# js220_fp_banana.net
KiCad netlist of a schematic drawn in EAGLE
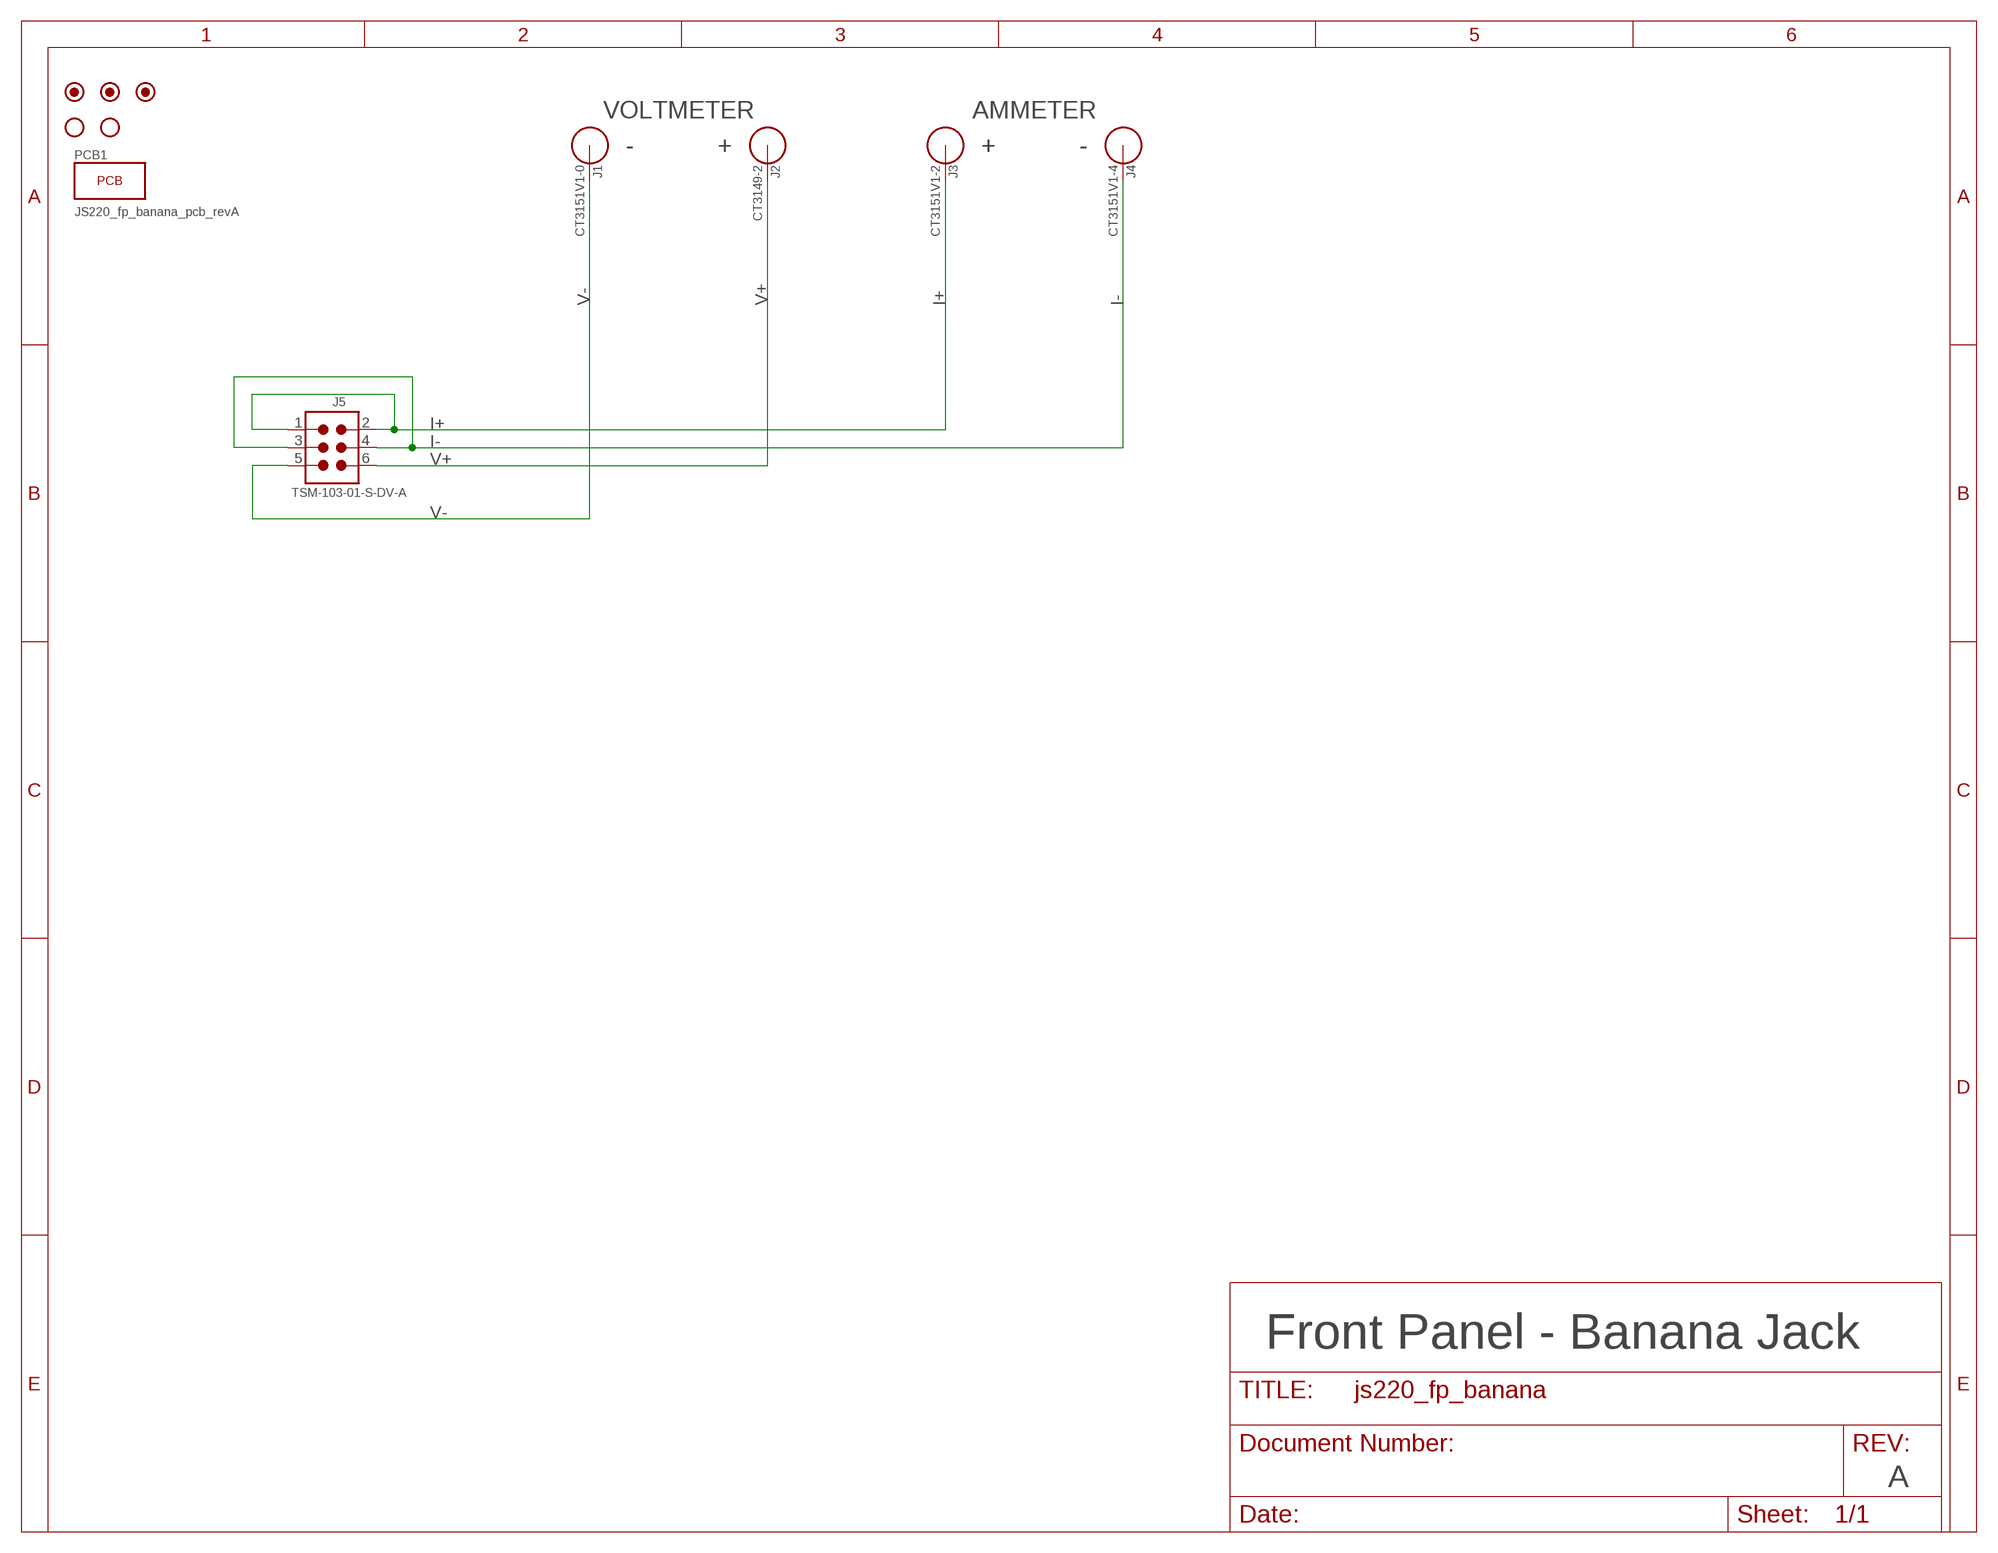
[diagram p0: schematic, sheet 1]

(export (version "E")
  (design (tool "Eeschema 10.0.6"))
  (components
    (comp (ref "FUD1")
      (value "FIDUCIAL_1MM")
      (footprint "eagle-import:FIDUCIAL_1MM_2MM")
      (libsource (lib "eagle-import") (part "FIDUCIAL_1MM"))
    )
    (comp (ref "FUD2")
      (value "FIDUCIAL_1MM")
      (footprint "eagle-import:FIDUCIAL_1MM_2MM")
      (libsource (lib "eagle-import") (part "FIDUCIAL_1MM"))
    )
    (comp (ref "FUD3")
      (value "FIDUCIAL_1MM")
      (footprint "eagle-import:FIDUCIAL_1MM_2MM")
      (libsource (lib "eagle-import") (part "FIDUCIAL_1MM"))
    )
    (comp (ref "H1")
      (value "HOLE_#6_NORESTRICT")
      (footprint "eagle-import:HOLE_3.5MM_NORESTRICT")
      (libsource (lib "eagle-import") (part "HOLE_#6_NORESTRICT"))
    )
    (comp (ref "H2")
      (value "HOLE_#6_NORESTRICT")
      (footprint "eagle-import:HOLE_3.5MM_NORESTRICT")
      (libsource (lib "eagle-import") (part "HOLE_#6_NORESTRICT"))
    )
    (comp (ref "J1")
      (value "CT3151V1-0")
      (footprint "eagle-import:CT3151V")
      (libsource (lib "eagle-import") (part "BANANA-JACK_CT3151V"))
    )
    (comp (ref "J2")
      (value "CT3149-2")
      (footprint "eagle-import:CT3151V")
      (fields (field (name "MPN") "CT3151V1-2"))
      (libsource (lib "eagle-import") (part "BANANA-JACK_CT3151V"))
    )
    (comp (ref "J3")
      (value "CT3151V1-2")
      (footprint "eagle-import:CT3151V")
      (libsource (lib "eagle-import") (part "BANANA-JACK_CT3151V"))
    )
    (comp (ref "J4")
      (value "CT3151V1-4")
      (footprint "eagle-import:CT3151V")
      (libsource (lib "eagle-import") (part "BANANA-JACK_CT3151V"))
    )
    (comp (ref "J5")
      (value "TSM-103-01-S-DV-A")
      (footprint "eagle-import:CONN_0.1_3X2_MSA")
      (libsource (lib "eagle-import") (part "CONN_0.1_3X2_MSA"))
    )
  )
  (nets
    (net (code "1") (name "/I+") (class "Default")
      (node (ref "J3") (pin "1") (pinfunction "1_1") (pintype "bidirectional"))
      (node (ref "J3") (pin "2") (pinfunction "1_2") (pintype "bidirectional"))
      (node (ref "J3") (pin "3") (pinfunction "1_3") (pintype "bidirectional"))
      (node (ref "J3") (pin "4") (pinfunction "1_4") (pintype "bidirectional"))
      (node (ref "J5") (pin "1") (pinfunction "1_1") (pintype "bidirectional"))
      (node (ref "J5") (pin "2") (pinfunction "2_2") (pintype "bidirectional"))
    )
    (net (code "2") (name "/I-") (class "Default")
      (node (ref "J4") (pin "1") (pinfunction "1_1") (pintype "bidirectional"))
      (node (ref "J4") (pin "2") (pinfunction "1_2") (pintype "bidirectional"))
      (node (ref "J4") (pin "3") (pinfunction "1_3") (pintype "bidirectional"))
      (node (ref "J4") (pin "4") (pinfunction "1_4") (pintype "bidirectional"))
      (node (ref "J5") (pin "3") (pinfunction "3_3") (pintype "bidirectional"))
      (node (ref "J5") (pin "4") (pinfunction "4_4") (pintype "bidirectional"))
    )
    (net (code "3") (name "/V+") (class "Default")
      (node (ref "J2") (pin "1") (pinfunction "1_1") (pintype "bidirectional"))
      (node (ref "J2") (pin "2") (pinfunction "1_2") (pintype "bidirectional"))
      (node (ref "J2") (pin "3") (pinfunction "1_3") (pintype "bidirectional"))
      (node (ref "J2") (pin "4") (pinfunction "1_4") (pintype "bidirectional"))
      (node (ref "J5") (pin "6") (pinfunction "6_6") (pintype "bidirectional"))
    )
    (net (code "4") (name "/V-") (class "Default")
      (node (ref "J1") (pin "1") (pinfunction "1_1") (pintype "bidirectional"))
      (node (ref "J1") (pin "2") (pinfunction "1_2") (pintype "bidirectional"))
      (node (ref "J1") (pin "3") (pinfunction "1_3") (pintype "bidirectional"))
      (node (ref "J1") (pin "4") (pinfunction "1_4") (pintype "bidirectional"))
      (node (ref "J5") (pin "5") (pinfunction "5_5") (pintype "bidirectional"))
    )
  )
)
